# 32.net
KiCad netlist of a schematic drawn in EasyEDA Pro
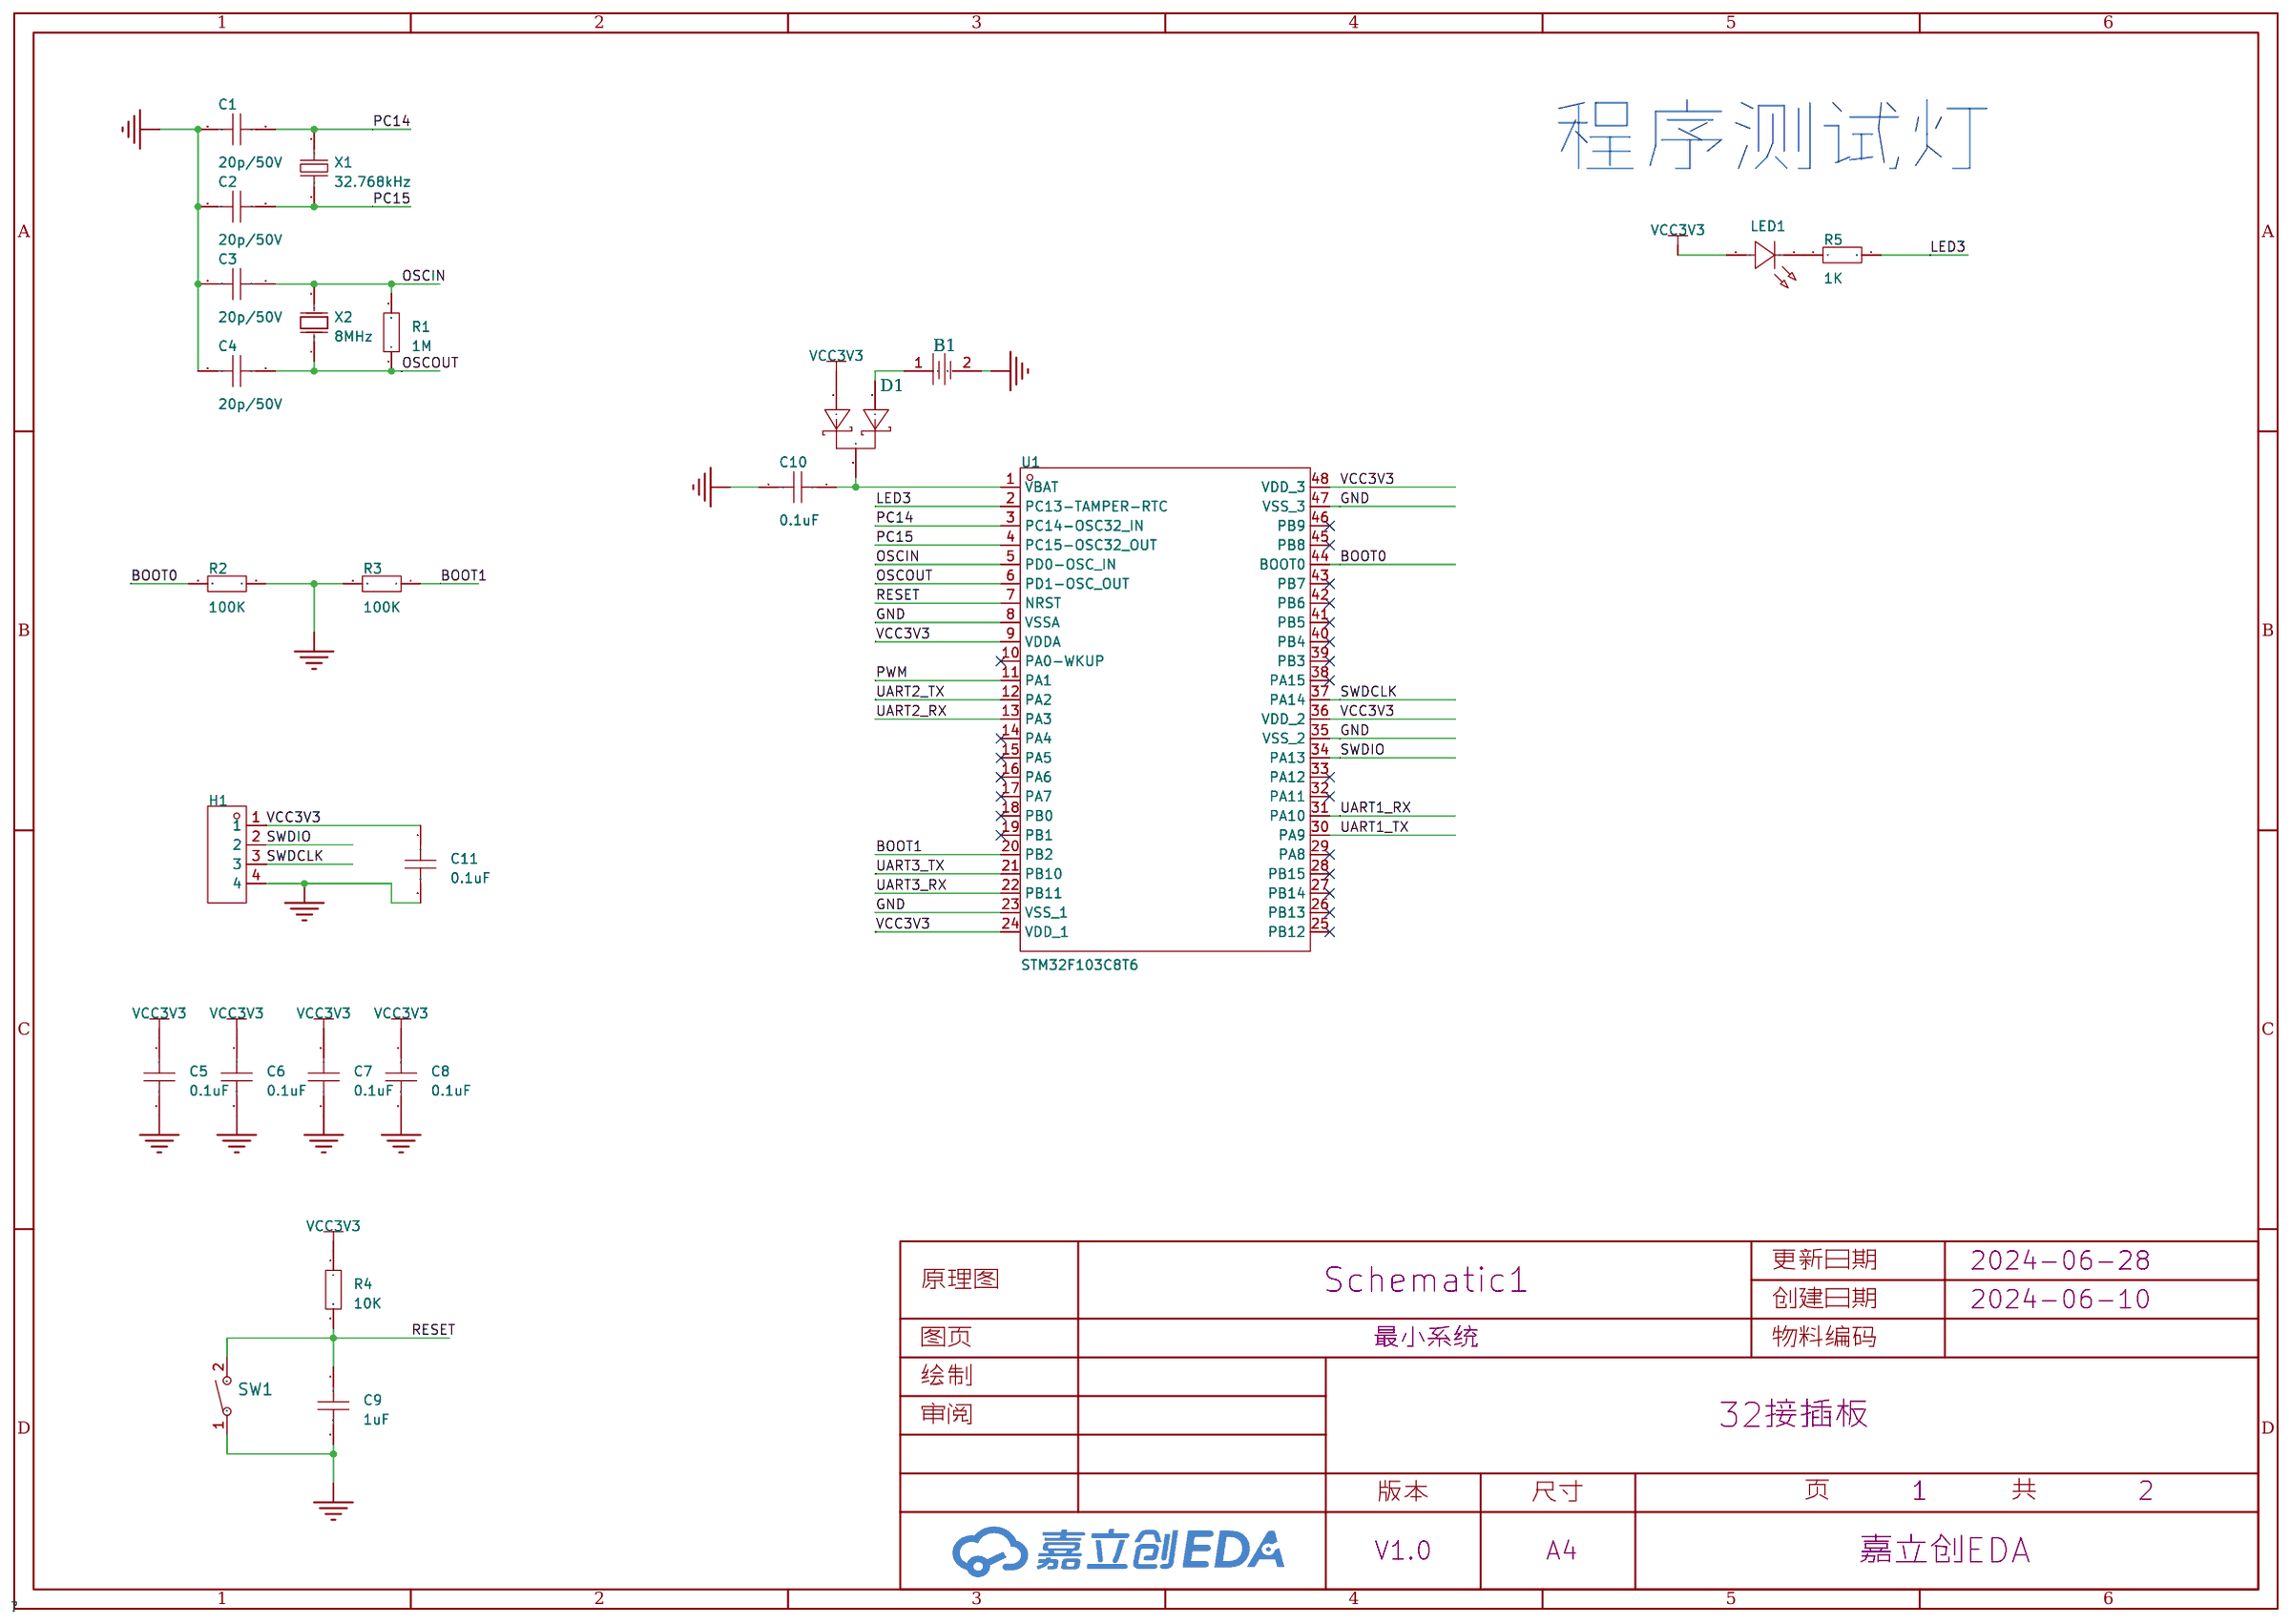
[diagram p0: 最小系统]
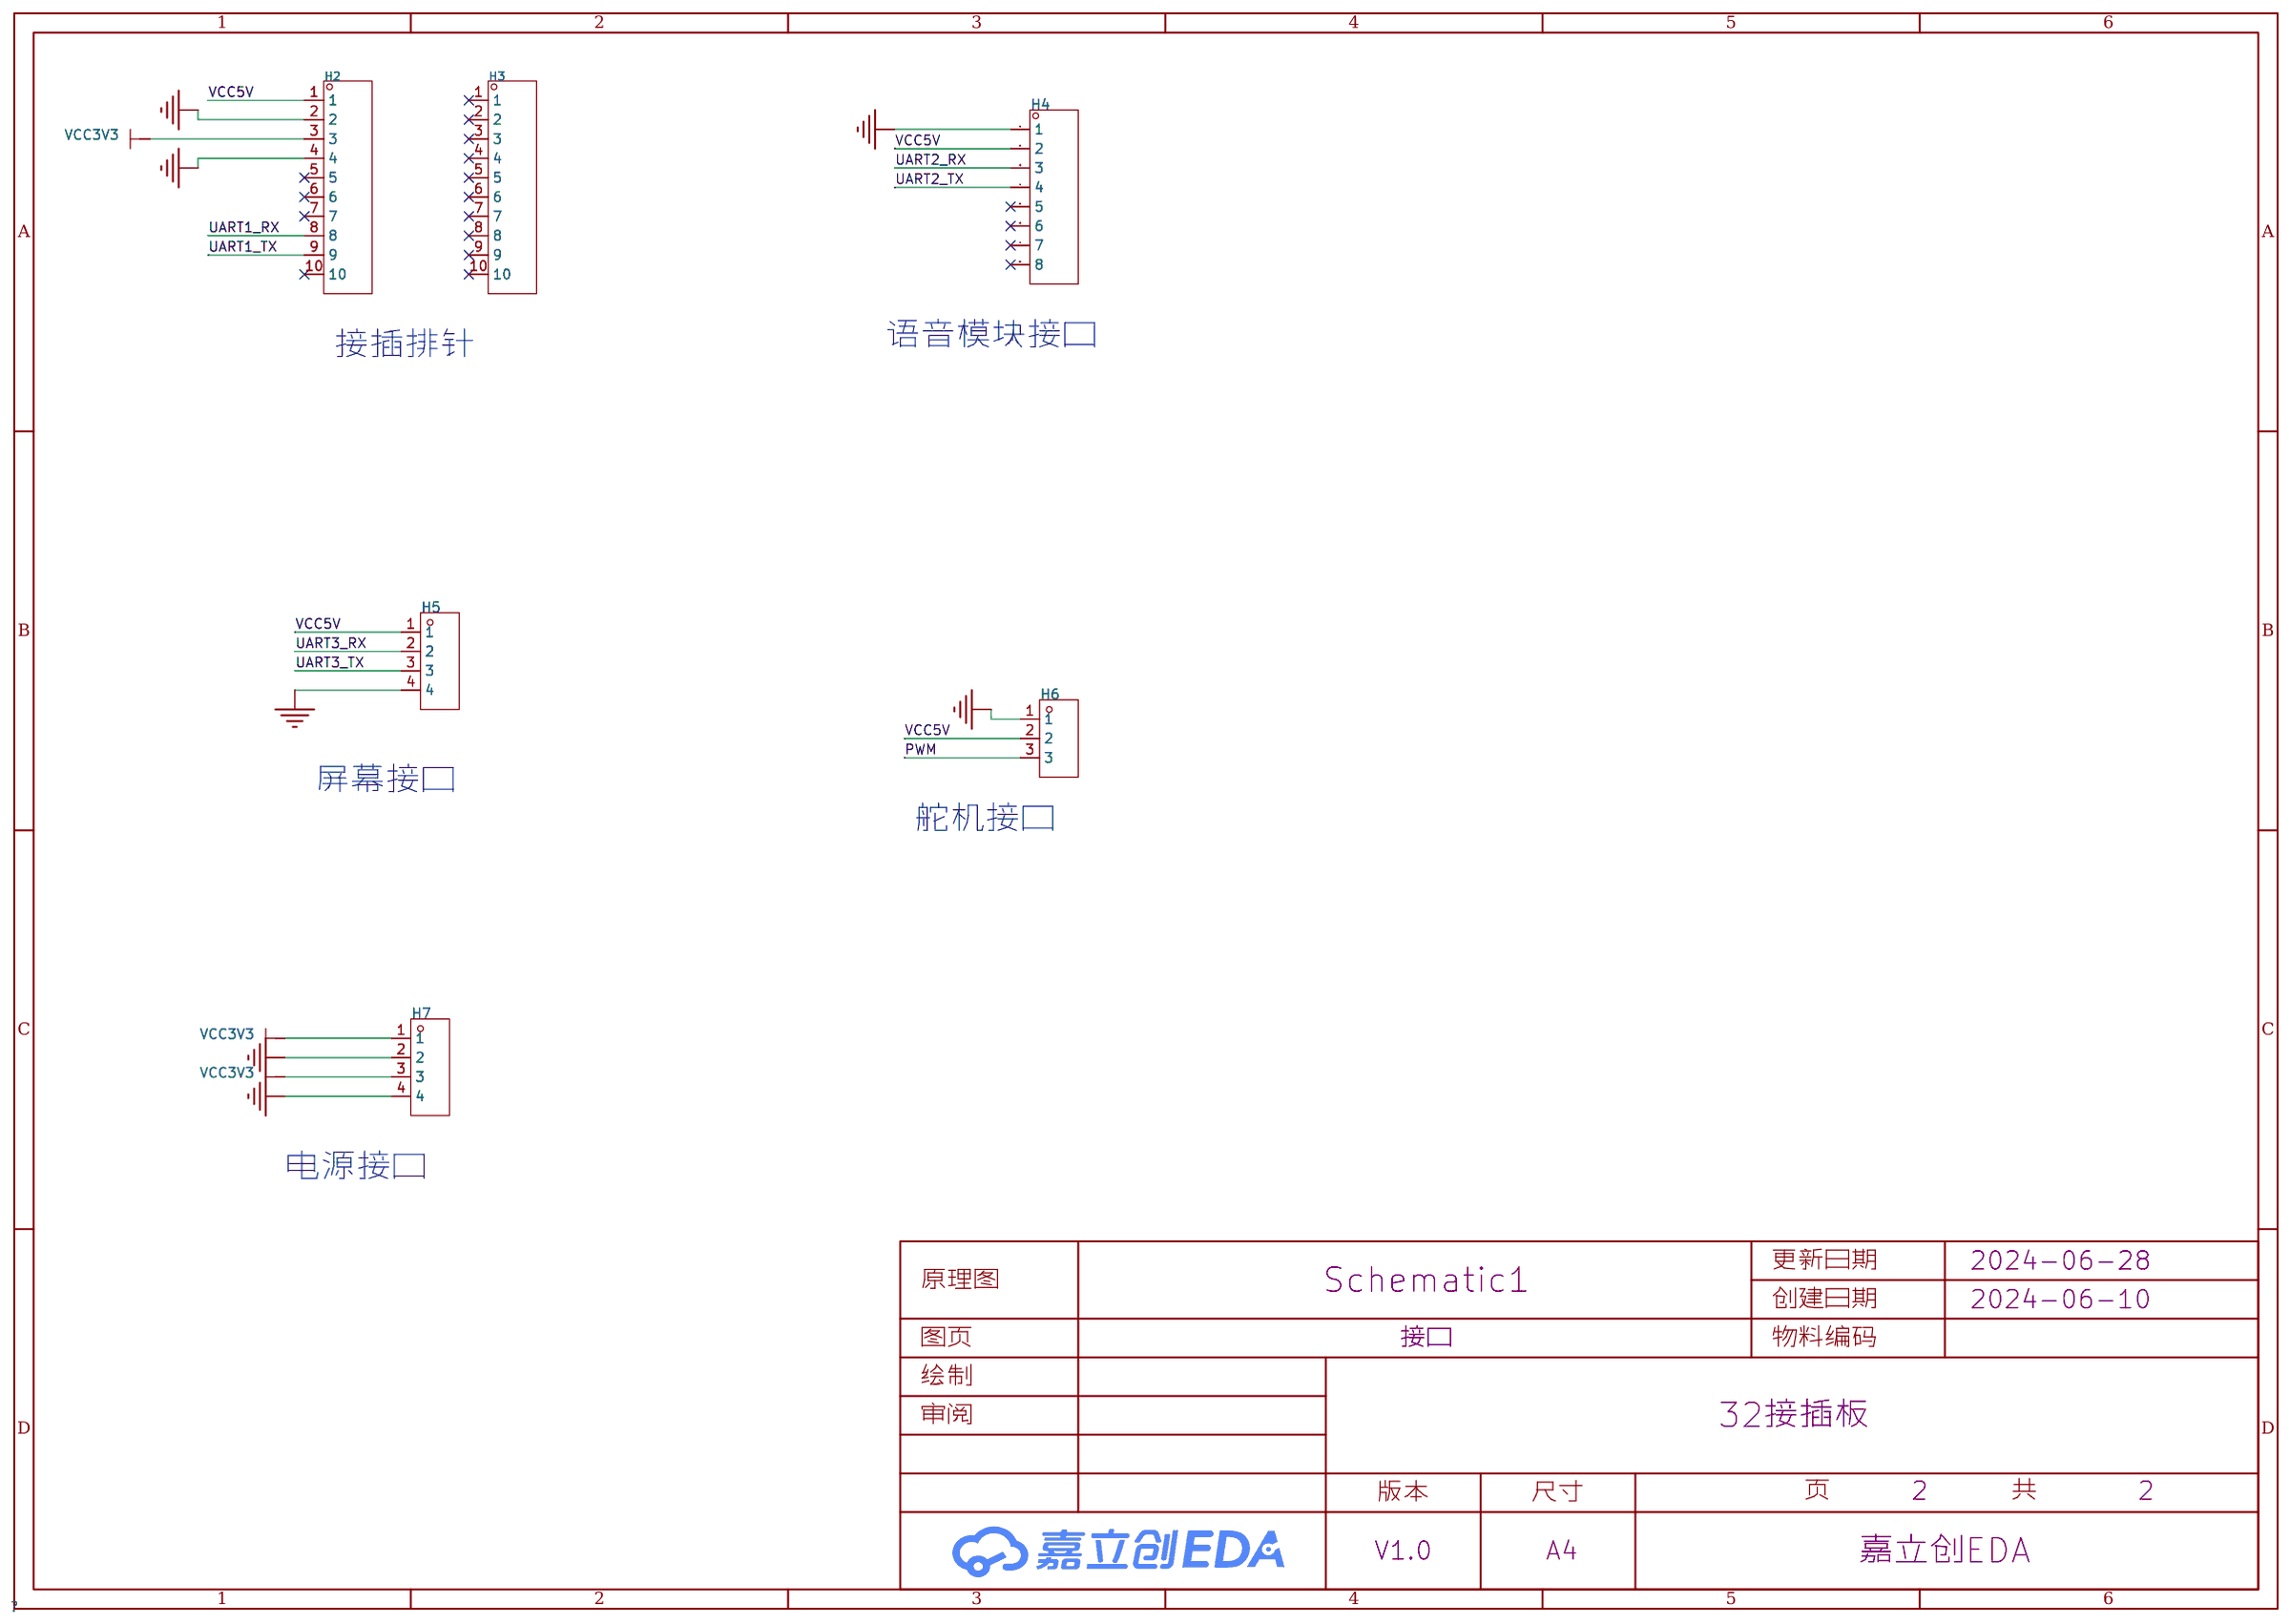
[diagram p1: 接口]

(export (version "E")
  (design (tool "Eeschema 10.0.6"))
  (components
    (comp (ref "B1")
      (value "CR1220-2")
      (footprint "easyedapro:BAT-SMD_CR1220-2")
      (description "连接器类型:电池底座;适用电池规格:CR1220;工作温度范围:-;")
      (fields (field (name "Manufacturer") "QJ"))
      (libsource (lib "easyedapro") (part "CR1220-2"))
    )
    (comp (ref "C1")
      (value "10uF/10V")
      (footprint "easyedapro:C0603")
      (description "容值:10uF;精度:±10%;额定电压:10V;材质(温度系数):X5R;")
      (fields
        (field (name "Manufacturer Part") "CL10A106KP8NNNC")
        (field (name "Manufacturer") "SAMSUNG(三星)")
      )
      (libsource (lib "easyedapro") (part "CL10A106KP8NNNC"))
    )
    (comp (ref "C2")
      (value "10uF/10V")
      (footprint "easyedapro:C0603")
      (description "容值:10uF;精度:±10%;额定电压:10V;材质(温度系数):X5R;")
      (fields
        (field (name "Manufacturer Part") "CL10A106KP8NNNC")
        (field (name "Manufacturer") "SAMSUNG(三星)")
      )
      (libsource (lib "easyedapro") (part "CL10A106KP8NNNC"))
    )
    (comp (ref "C3")
      (value "10uF/10V")
      (footprint "easyedapro:C0603")
      (description "容值:10uF;精度:±10%;额定电压:10V;材质(温度系数):X5R;")
      (fields
        (field (name "Manufacturer Part") "CL10A106KP8NNNC")
        (field (name "Manufacturer") "SAMSUNG(三星)")
      )
      (libsource (lib "easyedapro") (part "CL10A106KP8NNNC"))
    )
    (comp (ref "C4")
      (value "10uF/10V")
      (footprint "easyedapro:C0603")
      (description "容值:10uF;精度:±10%;额定电压:10V;材质(温度系数):X5R;")
      (fields
        (field (name "Manufacturer Part") "CL10A106KP8NNNC")
        (field (name "Manufacturer") "SAMSUNG(三星)")
      )
      (libsource (lib "easyedapro") (part "CL10A106KP8NNNC"))
    )
    (comp (ref "C5")
      (value "10uF/10V")
      (footprint "easyedapro:C0603")
      (description "容值:10uF;精度:±10%;额定电压:10V;材质(温度系数):X5R;")
      (fields
        (field (name "Manufacturer Part") "CL10A106KP8NNNC")
        (field (name "Manufacturer") "SAMSUNG(三星)")
      )
      (libsource (lib "easyedapro") (part "CL10A106KP8NNNC"))
    )
    (comp (ref "C6")
      (value "10uF/10V")
      (footprint "easyedapro:C0603")
      (description "容值:10uF;精度:±10%;额定电压:10V;材质(温度系数):X5R;")
      (fields
        (field (name "Manufacturer Part") "CL10A106KP8NNNC")
        (field (name "Manufacturer") "SAMSUNG(三星)")
      )
      (libsource (lib "easyedapro") (part "CL10A106KP8NNNC"))
    )
    (comp (ref "C7")
      (value "10uF/10V")
      (footprint "easyedapro:C0603")
      (description "容值:10uF;精度:±10%;额定电压:10V;材质(温度系数):X5R;")
      (fields
        (field (name "Manufacturer Part") "CL10A106KP8NNNC")
        (field (name "Manufacturer") "SAMSUNG(三星)")
      )
      (libsource (lib "easyedapro") (part "CL10A106KP8NNNC"))
    )
    (comp (ref "C8")
      (value "10uF/10V")
      (footprint "easyedapro:C0603")
      (description "容值:10uF;精度:±10%;额定电压:10V;材质(温度系数):X5R;")
      (fields
        (field (name "Manufacturer Part") "CL10A106KP8NNNC")
        (field (name "Manufacturer") "SAMSUNG(三星)")
      )
      (libsource (lib "easyedapro") (part "CL10A106KP8NNNC"))
    )
    (comp (ref "C9")
      (value "10uF/10V")
      (footprint "easyedapro:C0603")
      (description "容值:10uF;精度:±10%;额定电压:10V;材质(温度系数):X5R;")
      (fields
        (field (name "Manufacturer Part") "CL10A106KP8NNNC")
        (field (name "Manufacturer") "SAMSUNG(三星)")
      )
      (libsource (lib "easyedapro") (part "CL10A106KP8NNNC"))
    )
    (comp (ref "C10")
      (value "10uF/10V")
      (footprint "easyedapro:C0603")
      (description "容值:10uF;精度:±10%;额定电压:10V;材质(温度系数):X5R;")
      (fields
        (field (name "Manufacturer Part") "CL10A106KP8NNNC")
        (field (name "Manufacturer") "SAMSUNG(三星)")
      )
      (libsource (lib "easyedapro") (part "CL10A106KP8NNNC"))
    )
    (comp (ref "C11")
      (value "10uF/10V")
      (footprint "easyedapro:C0603")
      (description "容值:10uF;精度:±10%;额定电压:10V;材质(温度系数):X5R;")
      (fields
        (field (name "Manufacturer Part") "CL10A106KP8NNNC")
        (field (name "Manufacturer") "SAMSUNG(三星)")
      )
      (libsource (lib "easyedapro") (part "CL10A106KP8NNNC"))
    )
    (comp (ref "D1")
      (value "bat54ct")
      (footprint "easyedapro:SOT-523-3_L1.6-W0.8-P1.00-LS1.6-BR")
      (description "直流反向耐压(Vr):30V;平均整流电流(Io):200mA;正向压降(Vf):1V@100mA;")
      (fields (field (name "Manufacturer Part") "BAT54CT") (field (name "Manufacturer") "CJ（江苏长电/长晶）"))
      (libsource (lib "easyedapro") (part "bat54ct"))
    )
    (comp (ref "H1")
      (value "~")
      (footprint "easyedapro:HDR-TH_4P-P2.54-V-M")
      (libsource (lib "easyedapro") (part "PZ254V-11-04P"))
    )
    (comp (ref "LED1")
      (value "11-21/BHC-AQ2S2/2T")
      (footprint "easyedapro:LED-SMD_L3.0-W1.5-RD")
      (fields (field (name "Manufacturer") "EVERLIGHT(亿光)"))
      (libsource (lib "easyedapro") (part "11-21/BHC-AQ2S2/2T"))
    )
    (comp (ref "R1")
      (value "0Ω")
      (footprint "easyedapro:R0603")
      (description "电阻类型:厚膜电阻;阻值:0Ω;精度:±1%;功率:100mW;")
      (fields
        (field (name "Manufacturer Part") "0603WAF0000T5E")
        (field (name "Manufacturer") "UNI-ROYAL(厚声)")
      )
      (libsource (lib "easyedapro") (part "0603WAF0000T5E"))
    )
    (comp (ref "R2")
      (value "0Ω")
      (footprint "easyedapro:R0603")
      (description "电阻类型:厚膜电阻;阻值:0Ω;精度:±1%;功率:100mW;")
      (fields
        (field (name "Manufacturer Part") "0603WAF0000T5E")
        (field (name "Manufacturer") "UNI-ROYAL(厚声)")
      )
      (libsource (lib "easyedapro") (part "0603WAF0000T5E"))
    )
    (comp (ref "R3")
      (value "0Ω")
      (footprint "easyedapro:R0603")
      (description "电阻类型:厚膜电阻;阻值:0Ω;精度:±1%;功率:100mW;")
      (fields
        (field (name "Manufacturer Part") "0603WAF0000T5E")
        (field (name "Manufacturer") "UNI-ROYAL(厚声)")
      )
      (libsource (lib "easyedapro") (part "0603WAF0000T5E"))
    )
    (comp (ref "R4")
      (value "0Ω")
      (footprint "easyedapro:R0603")
      (description "电阻类型:厚膜电阻;阻值:0Ω;精度:±1%;功率:100mW;")
      (fields
        (field (name "Manufacturer Part") "0603WAF0000T5E")
        (field (name "Manufacturer") "UNI-ROYAL(厚声)")
      )
      (libsource (lib "easyedapro") (part "0603WAF0000T5E"))
    )
    (comp (ref "R5")
      (value "0Ω")
      (footprint "easyedapro:R0603")
      (description "电阻类型:厚膜电阻;阻值:0Ω;精度:±1%;功率:100mW;")
      (fields
        (field (name "Manufacturer Part") "0603WAF0000T5E")
        (field (name "Manufacturer") "UNI-ROYAL(厚声)")
      )
      (libsource (lib "easyedapro") (part "0603WAF0000T5E"))
    )
    (comp (ref "SW1")
      (value "按键贴片两脚（TS-1092S-B3D2-G ）")
      (footprint "easyedapro:SW-SMD_L6.1-W3.6-LS7.9")
      (fields (field (name "Manufacturer Part") "TS-1092S-B3D2-G") (field (name "Manufacturer") "Yuandi"))
      (libsource (lib "easyedapro") (part "按键贴片两脚（TS-1092S-B3D2-G ）"))
    )
    (comp (ref "U1")
      (value "STM32F103C8T6")
      (footprint "easyedapro:LQFP-48_L7.0-W7.0-P0.50-LS9.0-BL")
      (description "CPU内核:CM3;程序存储容量:64KB;RAM总容量:20KB;GPIO端口数量:37;工作电压范围:2V~3.6V;CPU最大主频:72MHz;程序存储器类型:FLASH;")
      (fields (field (name "Manufacturer") "ST(意法半导体)"))
      (libsource (lib "easyedapro") (part "STM32F103C8T6"))
    )
    (comp (ref "X1")
      (value "32.768kHz")
      (footprint "easyedapro:FC-135R_L3.2-W1.5")
      (description "晶振类型:贴片晶振;频率:32.768kHz;常温频差:±20ppm;外接负载电容:12.5pF;")
      (fields (field (name "Manufacturer Part") "Q13FC13500004") (field (name "Manufacturer") "EPSON(爱普生)"))
      (libsource (lib "easyedapro") (part "Q13FC1350000400"))
    )
    (comp (ref "X2")
      (value "8MHz")
      (footprint "easyedapro:CRYSTAL-SMD_L5.0-W3.2")
      (description "晶振类型:贴片晶振;频率:8MHz;常温频差:±10ppm;外接负载电容:20pF;频率稳定度(全温):±20ppm;")
      (fields (field (name "Manufacturer Part") "X50328MSB2GI") (field (name "Manufacturer") "YXC(扬兴晶振)"))
      (libsource (lib "easyedapro") (part "X50328MSB2GI"))
    )
    (comp (ref "H2")
      (value "~")
      (footprint "easyedapro:HDR-TH_10P-P2.54-V-M-1")
      (libsource (lib "easyedapro") (part "Header-Male-2.54_1x10"))
    )
    (comp (ref "H3")
      (value "~")
      (footprint "easyedapro:HDR-TH_10P-P2.54-V-M-1")
      (libsource (lib "easyedapro") (part "Header-Male-2.54_1x10"))
    )
    (comp (ref "H4")
      (value "~")
      (footprint "easyedapro:HDR-TH_8P-P2.54-V-M")
      (libsource (lib "easyedapro") (part "Header-Male-2.54_1x8"))
    )
    (comp (ref "H5")
      (value "~")
      (footprint "easyedapro:HDR-TH_4P-P2.54-V-M")
      (libsource (lib "easyedapro") (part "PZ254V-11-04P"))
    )
    (comp (ref "H6")
      (value "~")
      (footprint "easyedapro:HDR-TH_3P-P2.54-V-M")
      (libsource (lib "easyedapro") (part "PZ254V-11-03P_C2937625"))
    )
    (comp (ref "H7")
      (value "~")
      (footprint "easyedapro:HDR-TH_4P-P2.54-V-M")
      (libsource (lib "easyedapro") (part "PZ254V-11-04P"))
    )
  )
  (nets
    (net (code "1") (name "BOOT0") (class "Default")
      (node (ref "R2") (pin "2") (pinfunction "2_2") (pintype "input"))
      (node (ref "U1") (pin "44") (pinfunction "BOOT0_44") (pintype "unspecified"))
    )
    (net (code "2") (name "BOOT1") (class "Default")
      (node (ref "R3") (pin "1") (pinfunction "1_1") (pintype "input"))
      (node (ref "U1") (pin "20") (pinfunction "PB2_20") (pintype "unspecified"))
    )
    (net (code "3") (name "GND") (class "Default")
      (node (ref "B1") (pin "2") (pinfunction "2_2") (pintype "input"))
      (node (ref "C1") (pin "2") (pinfunction "2_2") (pintype "input"))
      (node (ref "C10") (pin "2") (pinfunction "2_2") (pintype "input"))
      (node (ref "C11") (pin "2") (pinfunction "2_2") (pintype "input"))
      (node (ref "C2") (pin "2") (pinfunction "2_2") (pintype "input"))
      (node (ref "C3") (pin "2") (pinfunction "2_2") (pintype "input"))
      (node (ref "C4") (pin "2") (pinfunction "2_2") (pintype "input"))
      (node (ref "C5") (pin "2") (pinfunction "2_2") (pintype "input"))
      (node (ref "C6") (pin "2") (pinfunction "2_2") (pintype "input"))
      (node (ref "C7") (pin "2") (pinfunction "2_2") (pintype "input"))
      (node (ref "C8") (pin "2") (pinfunction "2_2") (pintype "input"))
      (node (ref "C9") (pin "2") (pinfunction "2_2") (pintype "input"))
      (node (ref "H1") (pin "4") (pinfunction "4_4") (pintype "unspecified"))
      (node (ref "H2") (pin "2") (pinfunction "2_2") (pintype "input"))
      (node (ref "H2") (pin "4") (pinfunction "4_4") (pintype "input"))
      (node (ref "H4") (pin "1") (pinfunction "1_1") (pintype "unspecified"))
      (node (ref "H5") (pin "4") (pinfunction "4_4") (pintype "unspecified"))
      (node (ref "H6") (pin "1") (pinfunction "1_1") (pintype "input"))
      (node (ref "H7") (pin "2") (pinfunction "2_2") (pintype "unspecified"))
      (node (ref "H7") (pin "4") (pinfunction "4_4") (pintype "unspecified"))
      (node (ref "R2") (pin "1") (pinfunction "1_1") (pintype "input"))
      (node (ref "R3") (pin "2") (pinfunction "2_2") (pintype "input"))
      (node (ref "SW1") (pin "1") (pinfunction "1_1") (pintype "input"))
      (node (ref "U1") (pin "23") (pinfunction "VSS_1_23") (pintype "unspecified"))
      (node (ref "U1") (pin "35") (pinfunction "VSS_2_35") (pintype "unspecified"))
      (node (ref "U1") (pin "47") (pinfunction "VSS_3_47") (pintype "unspecified"))
      (node (ref "U1") (pin "8") (pinfunction "VSSA_8") (pintype "unspecified"))
    )
    (net (code "4") (name "LED3") (class "Default")
      (node (ref "R5") (pin "1") (pinfunction "1_1") (pintype "input"))
      (node (ref "U1") (pin "2") (pinfunction "PC13-TAMPER-RTC_2") (pintype "unspecified"))
    )
    (net (code "5") (name "Net-(B1-Pad1)") (class "Default")
      (node (ref "B1") (pin "1") (pinfunction "1_1") (pintype "input"))
      (node (ref "D1") (pin "1") (pinfunction "A_1") (pintype "input"))
    )
    (net (code "6") (name "Net-(D1-K)") (class "Default")
      (node (ref "C10") (pin "1") (pinfunction "1_1") (pintype "input"))
      (node (ref "D1") (pin "3") (pinfunction "K_3") (pintype "input"))
      (node (ref "U1") (pin "1") (pinfunction "VBAT_1") (pintype "unspecified"))
    )
    (net (code "7") (name "Net-(LED1-K)") (class "Default")
      (node (ref "LED1") (pin "1") (pinfunction "K_1") (pintype "input"))
      (node (ref "R5") (pin "2") (pinfunction "2_2") (pintype "input"))
    )
    (net (code "8") (name "OSCIN") (class "Default")
      (node (ref "C3") (pin "1") (pinfunction "1_1") (pintype "input"))
      (node (ref "R1") (pin "2") (pinfunction "2_2") (pintype "input"))
      (node (ref "U1") (pin "5") (pinfunction "PD0-OSC_IN_5") (pintype "unspecified"))
      (node (ref "X2") (pin "2") (pinfunction "OSC2_2") (pintype "input"))
    )
    (net (code "9") (name "OSCOUT") (class "Default")
      (node (ref "C4") (pin "1") (pinfunction "1_1") (pintype "input"))
      (node (ref "R1") (pin "1") (pinfunction "1_1") (pintype "input"))
      (node (ref "U1") (pin "6") (pinfunction "PD1-OSC_OUT_6") (pintype "unspecified"))
      (node (ref "X2") (pin "1") (pinfunction "OSC1_1") (pintype "input"))
    )
    (net (code "10") (name "PC14") (class "Default")
      (node (ref "C1") (pin "1") (pinfunction "1_1") (pintype "input"))
      (node (ref "U1") (pin "3") (pinfunction "PC14-OSC32_IN_3") (pintype "unspecified"))
      (node (ref "X1") (pin "1") (pinfunction "1_1") (pintype "unspecified"))
    )
    (net (code "11") (name "PC15") (class "Default")
      (node (ref "C2") (pin "1") (pinfunction "1_1") (pintype "input"))
      (node (ref "U1") (pin "4") (pinfunction "PC15-OSC32_OUT_4") (pintype "unspecified"))
      (node (ref "X1") (pin "2") (pinfunction "2_2") (pintype "unspecified"))
    )
    (net (code "12") (name "PWM") (class "Default")
      (node (ref "H6") (pin "3") (pinfunction "3_3") (pintype "input"))
      (node (ref "U1") (pin "11") (pinfunction "PA1_11") (pintype "unspecified"))
    )
    (net (code "13") (name "RESET") (class "Default")
      (node (ref "C9") (pin "1") (pinfunction "1_1") (pintype "input"))
      (node (ref "R4") (pin "2") (pinfunction "2_2") (pintype "input"))
      (node (ref "SW1") (pin "2") (pinfunction "2_2") (pintype "input"))
      (node (ref "U1") (pin "7") (pinfunction "NRST_7") (pintype "unspecified"))
    )
    (net (code "14") (name "SWDCLK") (class "Default")
      (node (ref "H1") (pin "3") (pinfunction "3_3") (pintype "unspecified"))
      (node (ref "U1") (pin "37") (pinfunction "PA14_37") (pintype "unspecified"))
    )
    (net (code "15") (name "SWDIO") (class "Default")
      (node (ref "H1") (pin "2") (pinfunction "2_2") (pintype "unspecified"))
      (node (ref "U1") (pin "34") (pinfunction "PA13_34") (pintype "unspecified"))
    )
    (net (code "16") (name "UART1_RX") (class "Default")
      (node (ref "H2") (pin "8") (pinfunction "8_8") (pintype "input"))
      (node (ref "U1") (pin "31") (pinfunction "PA10_31") (pintype "unspecified"))
    )
    (net (code "17") (name "UART1_TX") (class "Default")
      (node (ref "H2") (pin "9") (pinfunction "9_9") (pintype "input"))
      (node (ref "U1") (pin "30") (pinfunction "PA9_30") (pintype "unspecified"))
    )
    (net (code "18") (name "UART2_RX") (class "Default")
      (node (ref "H4") (pin "3") (pinfunction "3_3") (pintype "unspecified"))
      (node (ref "U1") (pin "13") (pinfunction "PA3_13") (pintype "unspecified"))
    )
    (net (code "19") (name "UART2_TX") (class "Default")
      (node (ref "H4") (pin "4") (pinfunction "4_4") (pintype "unspecified"))
      (node (ref "U1") (pin "12") (pinfunction "PA2_12") (pintype "unspecified"))
    )
    (net (code "20") (name "UART3_RX") (class "Default")
      (node (ref "H5") (pin "2") (pinfunction "2_2") (pintype "unspecified"))
      (node (ref "U1") (pin "22") (pinfunction "PB11_22") (pintype "unspecified"))
    )
    (net (code "21") (name "UART3_TX") (class "Default")
      (node (ref "H5") (pin "3") (pinfunction "3_3") (pintype "unspecified"))
      (node (ref "U1") (pin "21") (pinfunction "PB10_21") (pintype "unspecified"))
    )
    (net (code "22") (name "VCC3V3") (class "Default")
      (node (ref "C11") (pin "1") (pinfunction "1_1") (pintype "input"))
      (node (ref "C5") (pin "1") (pinfunction "1_1") (pintype "input"))
      (node (ref "C6") (pin "1") (pinfunction "1_1") (pintype "input"))
      (node (ref "C7") (pin "1") (pinfunction "1_1") (pintype "input"))
      (node (ref "C8") (pin "1") (pinfunction "1_1") (pintype "input"))
      (node (ref "D1") (pin "2") (pinfunction "A_2") (pintype "input"))
      (node (ref "H1") (pin "1") (pinfunction "1_1") (pintype "unspecified"))
      (node (ref "H2") (pin "3") (pinfunction "3_3") (pintype "input"))
      (node (ref "H7") (pin "1") (pinfunction "1_1") (pintype "unspecified"))
      (node (ref "H7") (pin "3") (pinfunction "3_3") (pintype "unspecified"))
      (node (ref "LED1") (pin "2") (pinfunction "A_2") (pintype "input"))
      (node (ref "R4") (pin "1") (pinfunction "1_1") (pintype "input"))
      (node (ref "U1") (pin "24") (pinfunction "VDD_1_24") (pintype "unspecified"))
      (node (ref "U1") (pin "36") (pinfunction "VDD_2_36") (pintype "unspecified"))
      (node (ref "U1") (pin "48") (pinfunction "VDD_3_48") (pintype "unspecified"))
      (node (ref "U1") (pin "9") (pinfunction "VDDA_9") (pintype "unspecified"))
    )
    (net (code "23") (name "VCC5V") (class "Default")
      (node (ref "H2") (pin "1") (pinfunction "1_1") (pintype "input"))
      (node (ref "H4") (pin "2") (pinfunction "2_2") (pintype "unspecified"))
      (node (ref "H5") (pin "1") (pinfunction "1_1") (pintype "unspecified"))
      (node (ref "H6") (pin "2") (pinfunction "2_2") (pintype "input"))
    )
    (net (code "24") (name "unconnected-(H2-Pad5)") (class "Default")
      (node (ref "H2") (pin "5") (pinfunction "5_5") (pintype "input+no_connect"))
    )
    (net (code "25") (name "unconnected-(H2-Pad6)") (class "Default")
      (node (ref "H2") (pin "6") (pinfunction "6_6") (pintype "input+no_connect"))
    )
    (net (code "26") (name "unconnected-(H2-Pad7)") (class "Default")
      (node (ref "H2") (pin "7") (pinfunction "7_7") (pintype "input+no_connect"))
    )
    (net (code "27") (name "unconnected-(H2-Pad10)") (class "Default")
      (node (ref "H2") (pin "10") (pinfunction "10_10") (pintype "input+no_connect"))
    )
    (net (code "28") (name "unconnected-(H3-Pad1)") (class "Default")
      (node (ref "H3") (pin "1") (pinfunction "1_1") (pintype "input+no_connect"))
    )
    (net (code "29") (name "unconnected-(H3-Pad2)") (class "Default")
      (node (ref "H3") (pin "2") (pinfunction "2_2") (pintype "input+no_connect"))
    )
    (net (code "30") (name "unconnected-(H3-Pad3)") (class "Default")
      (node (ref "H3") (pin "3") (pinfunction "3_3") (pintype "input+no_connect"))
    )
    (net (code "31") (name "unconnected-(H3-Pad4)") (class "Default")
      (node (ref "H3") (pin "4") (pinfunction "4_4") (pintype "input+no_connect"))
    )
    (net (code "32") (name "unconnected-(H3-Pad5)") (class "Default")
      (node (ref "H3") (pin "5") (pinfunction "5_5") (pintype "input+no_connect"))
    )
    (net (code "33") (name "unconnected-(H3-Pad6)") (class "Default")
      (node (ref "H3") (pin "6") (pinfunction "6_6") (pintype "input+no_connect"))
    )
    (net (code "34") (name "unconnected-(H3-Pad7)") (class "Default")
      (node (ref "H3") (pin "7") (pinfunction "7_7") (pintype "input+no_connect"))
    )
    (net (code "35") (name "unconnected-(H3-Pad8)") (class "Default")
      (node (ref "H3") (pin "8") (pinfunction "8_8") (pintype "input+no_connect"))
    )
    (net (code "36") (name "unconnected-(H3-Pad9)") (class "Default")
      (node (ref "H3") (pin "9") (pinfunction "9_9") (pintype "input+no_connect"))
    )
    (net (code "37") (name "unconnected-(H3-Pad10)") (class "Default")
      (node (ref "H3") (pin "10") (pinfunction "10_10") (pintype "input+no_connect"))
    )
    (net (code "38") (name "unconnected-(H4-Pad5)") (class "Default")
      (node (ref "H4") (pin "5") (pinfunction "5_5") (pintype "unspecified+no_connect"))
    )
    (net (code "39") (name "unconnected-(H4-Pad6)") (class "Default")
      (node (ref "H4") (pin "6") (pinfunction "6_6") (pintype "unspecified+no_connect"))
    )
    (net (code "40") (name "unconnected-(H4-Pad7)") (class "Default")
      (node (ref "H4") (pin "7") (pinfunction "7_7") (pintype "unspecified+no_connect"))
    )
    (net (code "41") (name "unconnected-(H4-Pad8)") (class "Default")
      (node (ref "H4") (pin "8") (pinfunction "8_8") (pintype "unspecified+no_connect"))
    )
    (net (code "42") (name "unconnected-(U1-PA0-WKUP-Pad10)") (class "Default")
      (node (ref "U1") (pin "10") (pinfunction "PA0-WKUP_10") (pintype "unspecified+no_connect"))
    )
    (net (code "43") (name "unconnected-(U1-PA4-Pad14)") (class "Default")
      (node (ref "U1") (pin "14") (pinfunction "PA4_14") (pintype "unspecified+no_connect"))
    )
    (net (code "44") (name "unconnected-(U1-PA5-Pad15)") (class "Default")
      (node (ref "U1") (pin "15") (pinfunction "PA5_15") (pintype "unspecified+no_connect"))
    )
    (net (code "45") (name "unconnected-(U1-PA6-Pad16)") (class "Default")
      (node (ref "U1") (pin "16") (pinfunction "PA6_16") (pintype "unspecified+no_connect"))
    )
    (net (code "46") (name "unconnected-(U1-PA7-Pad17)") (class "Default")
      (node (ref "U1") (pin "17") (pinfunction "PA7_17") (pintype "unspecified+no_connect"))
    )
    (net (code "47") (name "unconnected-(U1-PA8-Pad29)") (class "Default")
      (node (ref "U1") (pin "29") (pinfunction "PA8_29") (pintype "unspecified+no_connect"))
    )
    (net (code "48") (name "unconnected-(U1-PA11-Pad32)") (class "Default")
      (node (ref "U1") (pin "32") (pinfunction "PA11_32") (pintype "unspecified+no_connect"))
    )
    (net (code "49") (name "unconnected-(U1-PA12-Pad33)") (class "Default")
      (node (ref "U1") (pin "33") (pinfunction "PA12_33") (pintype "unspecified+no_connect"))
    )
    (net (code "50") (name "unconnected-(U1-PA15-Pad38)") (class "Default")
      (node (ref "U1") (pin "38") (pinfunction "PA15_38") (pintype "unspecified+no_connect"))
    )
    (net (code "51") (name "unconnected-(U1-PB0-Pad18)") (class "Default")
      (node (ref "U1") (pin "18") (pinfunction "PB0_18") (pintype "unspecified+no_connect"))
    )
    (net (code "52") (name "unconnected-(U1-PB1-Pad19)") (class "Default")
      (node (ref "U1") (pin "19") (pinfunction "PB1_19") (pintype "unspecified+no_connect"))
    )
    (net (code "53") (name "unconnected-(U1-PB3-Pad39)") (class "Default")
      (node (ref "U1") (pin "39") (pinfunction "PB3_39") (pintype "unspecified+no_connect"))
    )
    (net (code "54") (name "unconnected-(U1-PB4-Pad40)") (class "Default")
      (node (ref "U1") (pin "40") (pinfunction "PB4_40") (pintype "unspecified+no_connect"))
    )
    (net (code "55") (name "unconnected-(U1-PB5-Pad41)") (class "Default")
      (node (ref "U1") (pin "41") (pinfunction "PB5_41") (pintype "unspecified+no_connect"))
    )
    (net (code "56") (name "unconnected-(U1-PB6-Pad42)") (class "Default")
      (node (ref "U1") (pin "42") (pinfunction "PB6_42") (pintype "unspecified+no_connect"))
    )
    (net (code "57") (name "unconnected-(U1-PB7-Pad43)") (class "Default")
      (node (ref "U1") (pin "43") (pinfunction "PB7_43") (pintype "unspecified+no_connect"))
    )
    (net (code "58") (name "unconnected-(U1-PB8-Pad45)") (class "Default")
      (node (ref "U1") (pin "45") (pinfunction "PB8_45") (pintype "unspecified+no_connect"))
    )
    (net (code "59") (name "unconnected-(U1-PB9-Pad46)") (class "Default")
      (node (ref "U1") (pin "46") (pinfunction "PB9_46") (pintype "unspecified+no_connect"))
    )
    (net (code "60") (name "unconnected-(U1-PB12-Pad25)") (class "Default")
      (node (ref "U1") (pin "25") (pinfunction "PB12_25") (pintype "unspecified+no_connect"))
    )
    (net (code "61") (name "unconnected-(U1-PB13-Pad26)") (class "Default")
      (node (ref "U1") (pin "26") (pinfunction "PB13_26") (pintype "unspecified+no_connect"))
    )
    (net (code "62") (name "unconnected-(U1-PB14-Pad27)") (class "Default")
      (node (ref "U1") (pin "27") (pinfunction "PB14_27") (pintype "unspecified+no_connect"))
    )
    (net (code "63") (name "unconnected-(U1-PB15-Pad28)") (class "Default")
      (node (ref "U1") (pin "28") (pinfunction "PB15_28") (pintype "unspecified+no_connect"))
    )
  )
)
